# PowerSupplies.net
KiCad netlist of a schematic drawn in Altium Designer
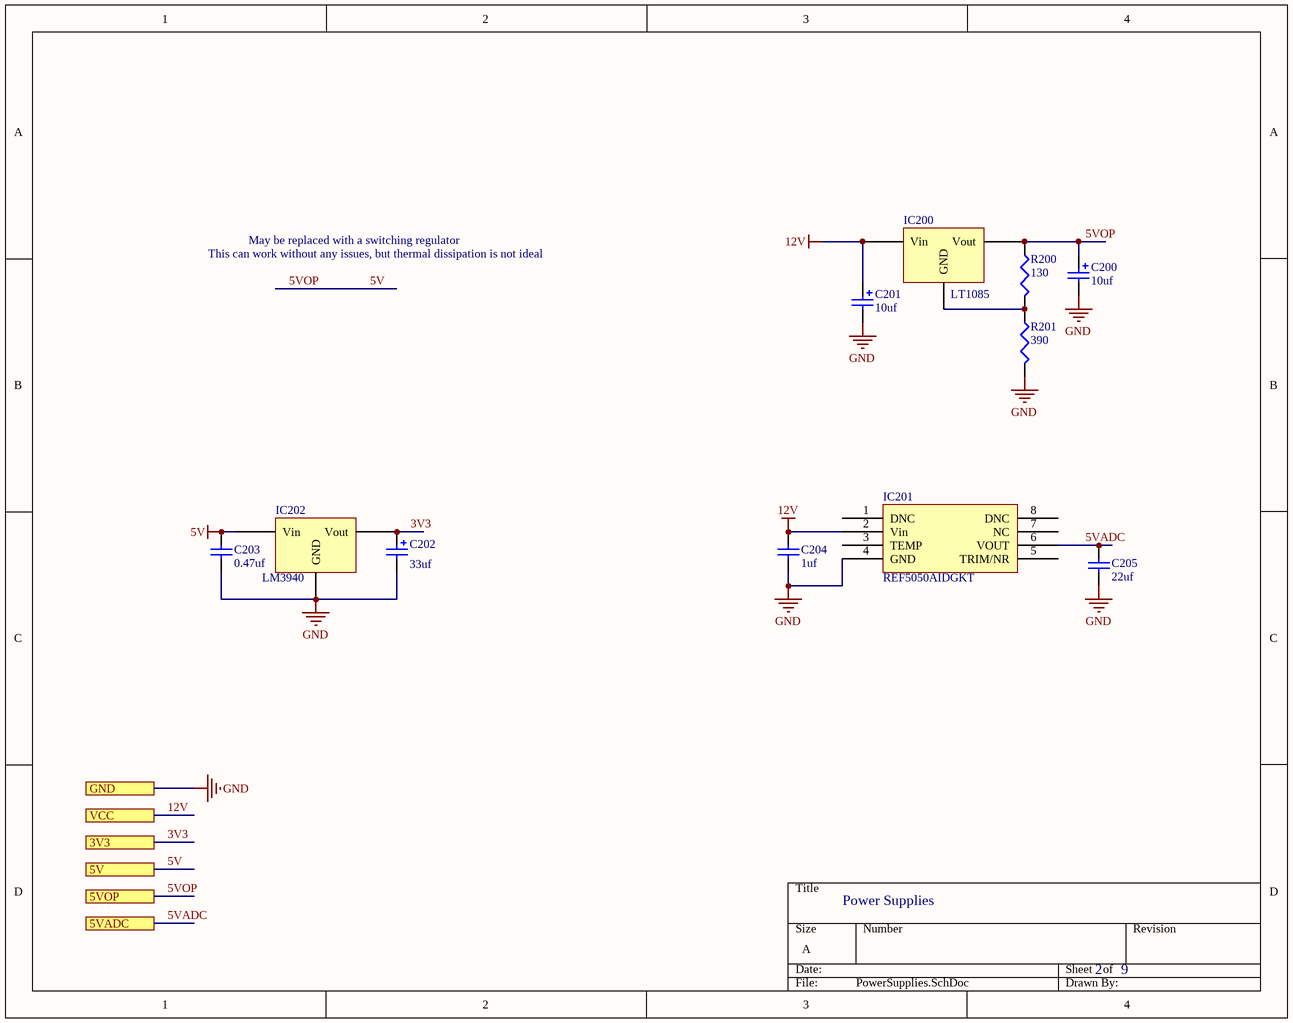
[diagram p0: PowerSupplies.SchDoc]

(export (version "E")
  (design (tool "Eeschema 10.0.6"))
  (components
    (comp (ref "C200")
      (value "10uf")
      (footprint "SMD1206 Polarized")
      (description "Polarized Capacitor (Surface Mount)")
      (fields (field (name "Comment") "Cap"))
      (libsource (lib "Components") (part "Capacitor Polarized"))
    )
    (comp (ref "C201")
      (value "10uf")
      (footprint "SMD1206 Polarized")
      (description "Polarized Capacitor (Surface Mount)")
      (fields (field (name "Comment") "Cap"))
      (libsource (lib "Components") (part "Capacitor Polarized"))
    )
    (comp (ref "C202")
      (value "33uf")
      (footprint "SMD1206 Polarized")
      (description "Polarized Capacitor (Surface Mount)")
      (fields (field (name "Comment") "Cap"))
      (libsource (lib "Components") (part "Capacitor Polarized"))
    )
    (comp (ref "C203")
      (value "0.47uf")
      (footprint "SMD0603")
      (description "Ceramic Chip Capacitor")
      (fields (field (name "Comment") "Cap"))
      (libsource (lib "Components") (part "Capacitor Ceramic"))
    )
    (comp (ref "C204")
      (value "1uf")
      (footprint "SMD0603")
      (description "Ceramic Chip Capacitor")
      (fields (field (name "Comment") "Capacitor Ceramic"))
      (libsource (lib "Components") (part "Capacitor Ceramic"))
    )
    (comp (ref "C205")
      (value "22uf")
      (footprint "SMD1206")
      (description "Ceramic Chip Capacitor")
      (fields (field (name "Comment") "Capacitor Ceramic"))
      (libsource (lib "Components") (part "Capacitor Ceramic"))
    )
    (comp (ref "IC200")
      (value "LT1085")
      (footprint "DPAK - 3pin")
      (description "3A DC/DC Converter (SM)")
      (libsource (lib "Components") (part "LT1085"))
    )
    (comp (ref "IC201")
      (value "REF5050AIDGKT")
      (footprint "VSSOP-8 (DGK)")
      (description "5V Precision Reference Voltage")
      (libsource (lib "Components") (part "REF5050AIDGKT"))
    )
    (comp (ref "IC202")
      (value "LM3940")
      (footprint "SOT-223")
      (description "3.3V 1A LDO")
      (libsource (lib "Components") (part "LM3940"))
    )
    (comp (ref "R200")
      (value "130")
      (footprint "SMD0603")
      (description "Resistor")
      (fields (field (name "Comment") "Res"))
      (libsource (lib "Components") (part "Resistor"))
    )
    (comp (ref "R201")
      (value "390")
      (footprint "SMD0603")
      (description "Resistor")
      (fields (field (name "Comment") "Res"))
      (libsource (lib "Components") (part "Resistor"))
    )
  )
  (nets
    (net (code "1") (name "/3V3") (class "Default")
      (node (ref "C202") (pin "1") (pinfunction "1_1") (pintype "passive"))
      (node (ref "IC202") (pin "Vout") (pinfunction "Vout_Vout") (pintype "passive"))
    )
    (net (code "2") (name "/5VADC") (class "Default")
      (node (ref "C205") (pin "2") (pinfunction "2_2") (pintype "passive"))
      (node (ref "IC201") (pin "6") (pinfunction "VOUT_6") (pintype "passive"))
    )
    (net (code "3") (name "5V") (class "Default")
      (node (ref "C200") (pin "1") (pinfunction "1_1") (pintype "passive"))
      (node (ref "C203") (pin "2") (pinfunction "2_2") (pintype "passive"))
      (node (ref "IC200") (pin "Vout") (pinfunction "Vout_Vout") (pintype "passive"))
      (node (ref "IC202") (pin "Vin") (pinfunction "Vin_Vin") (pintype "passive"))
      (node (ref "R200") (pin "1") (pinfunction "1_1") (pintype "passive"))
    )
    (net (code "4") (name "12V") (class "Default")
      (node (ref "C201") (pin "1") (pinfunction "1_1") (pintype "passive"))
      (node (ref "C204") (pin "2") (pinfunction "2_2") (pintype "passive"))
      (node (ref "IC200") (pin "Vin") (pinfunction "Vin_Vin") (pintype "passive"))
      (node (ref "IC201") (pin "2") (pinfunction "Vin_2") (pintype "passive"))
    )
    (net (code "5") (name "GND") (class "Default")
      (node (ref "C200") (pin "2") (pinfunction "2_2") (pintype "passive"))
      (node (ref "C201") (pin "2") (pinfunction "2_2") (pintype "passive"))
      (node (ref "C202") (pin "2") (pinfunction "2_2") (pintype "passive"))
      (node (ref "C203") (pin "1") (pinfunction "1_1") (pintype "passive"))
      (node (ref "C204") (pin "1") (pinfunction "1_1") (pintype "passive"))
      (node (ref "C205") (pin "1") (pinfunction "1_1") (pintype "passive"))
      (node (ref "IC201") (pin "4") (pinfunction "GND_4") (pintype "passive"))
      (node (ref "IC202") (pin "GND") (pinfunction "GND_GND") (pintype "passive"))
      (node (ref "R201") (pin "2") (pinfunction "2_2") (pintype "passive"))
    )
    (net (code "6") (name "Net-(IC200-PadGND)") (class "Default")
      (node (ref "IC200") (pin "GND") (pinfunction "GND_GND") (pintype "passive"))
      (node (ref "R200") (pin "2") (pinfunction "2_2") (pintype "passive"))
      (node (ref "R201") (pin "1") (pinfunction "1_1") (pintype "passive"))
    )
    (net (code "7") (name "unconnected-(IC201-DNC-Pad1)") (class "Default")
      (node (ref "IC201") (pin "1") (pinfunction "DNC_1") (pintype "passive"))
    )
    (net (code "8") (name "unconnected-(IC201-DNC-Pad8)") (class "Default")
      (node (ref "IC201") (pin "8") (pinfunction "DNC_8") (pintype "passive"))
    )
    (net (code "9") (name "unconnected-(IC201-NC-Pad7)") (class "Default")
      (node (ref "IC201") (pin "7") (pinfunction "NC_7") (pintype "passive"))
    )
    (net (code "10") (name "unconnected-(IC201-TEMP-Pad3)") (class "Default")
      (node (ref "IC201") (pin "3") (pinfunction "TEMP_3") (pintype "passive"))
    )
    (net (code "11") (name "unconnected-(IC201-TRIM{slash}NR-Pad5)") (class "Default")
      (node (ref "IC201") (pin "5") (pinfunction "TRIM/NR_5") (pintype "passive"))
    )
  )
)
